# ingredionradar.net
KiCad netlist of a schematic drawn in Altium Designer
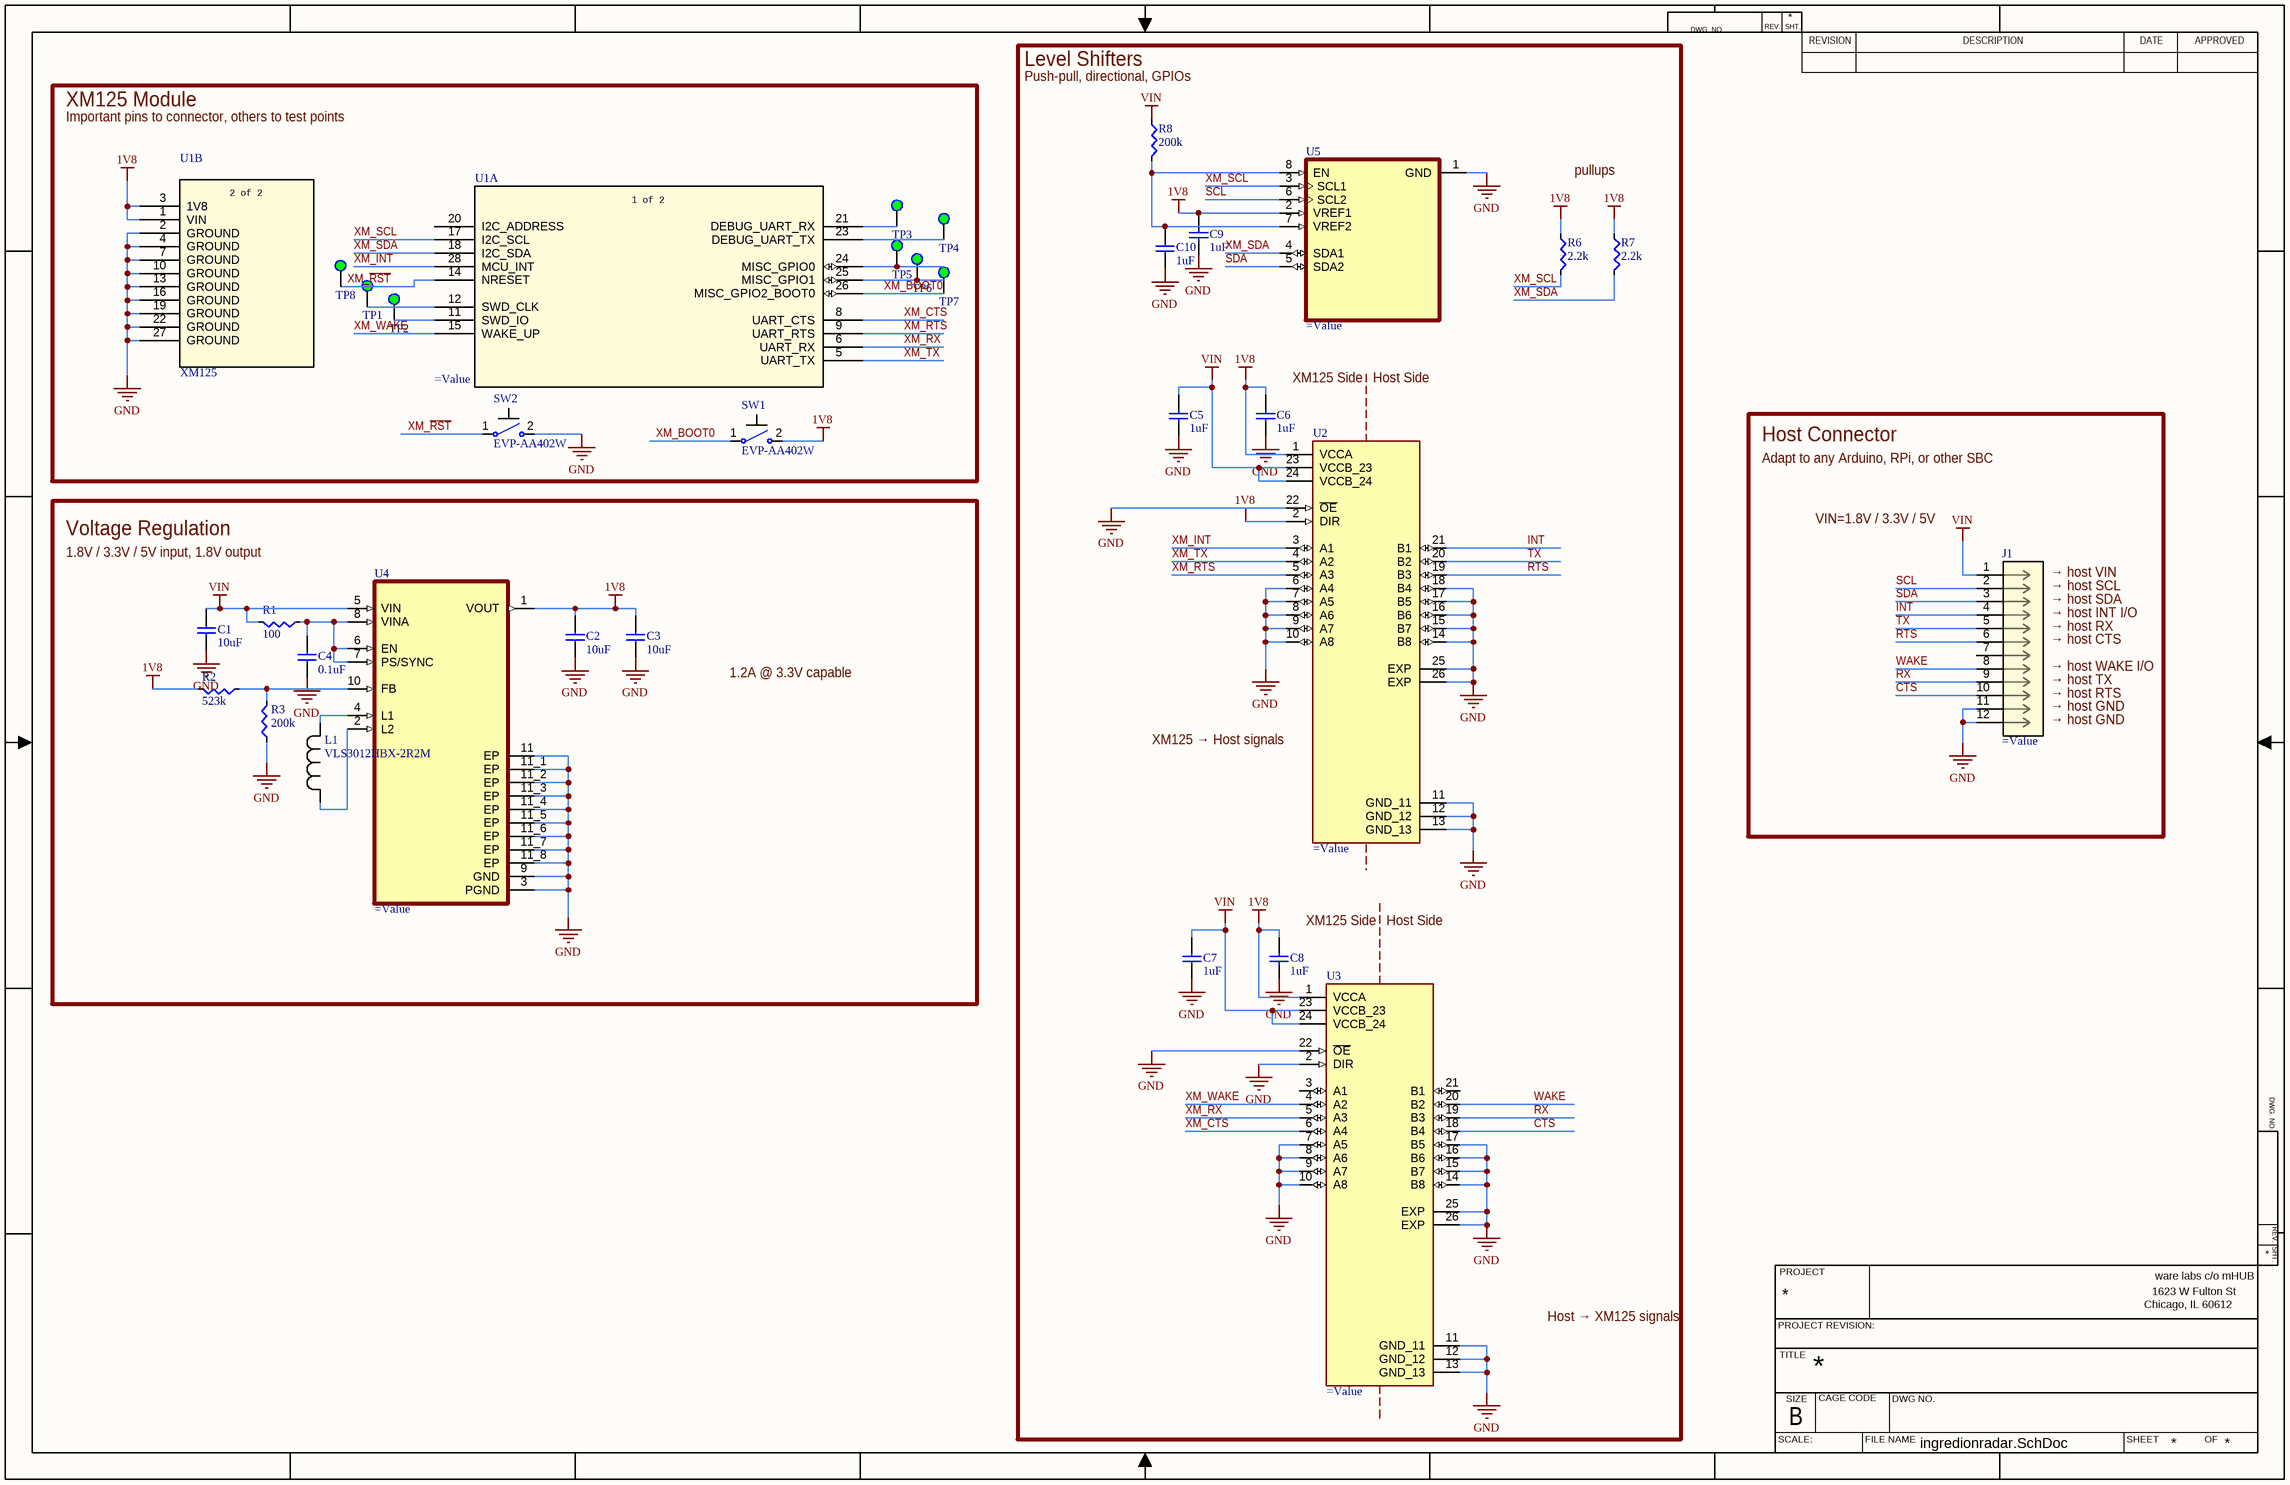
[diagram p0: ingredionradar.SchDoc]

(export (version "E")
  (design (tool "Eeschema 10.0.6"))
  (components
    (comp (ref "C1")
      (value "10uF")
      (footprint "CAP0603")
      (description "Chip Capacitor")
      (fields
        (field (name "MANUFACTURER") "Samsung Electro-Mechanics")
        (field (name "PART NUMBER") "CL10X106MO8NRNC")
      )
      (libsource (lib "ware") (part "CAP"))
    )
    (comp (ref "C2")
      (value "10uF")
      (footprint "CAP0603")
      (description "Chip Capacitor")
      (fields
        (field (name "MANUFACTURER") "Samsung Electro-Mechanics")
        (field (name "PART NUMBER") "CL10X106MO8NRNC")
      )
      (libsource (lib "ware") (part "CAP"))
    )
    (comp (ref "C3")
      (value "10uF")
      (footprint "CAP0603")
      (description "Chip Capacitor")
      (fields
        (field (name "MANUFACTURER") "Samsung Electro-Mechanics")
        (field (name "PART NUMBER") "CL10X106MO8NRNC")
      )
      (libsource (lib "ware") (part "CAP"))
    )
    (comp (ref "C4")
      (value "0.1uF")
      (footprint "CAP0402")
      (description "Chip Capacitor")
      (fields
        (field (name "MANUFACTURER") "Samsung Electro-Mechanics")
        (field (name "PART NUMBER") "CL05B104KP5NNNC")
      )
      (libsource (lib "ware") (part "CAP"))
    )
    (comp (ref "C5")
      (value "1uF")
      (footprint "CAP0402")
      (description "Chip Capacitor")
      (fields
        (field (name "MANUFACTURER") "Samsung Electro-Mechanics")
        (field (name "PART NUMBER") "CL05B105KQ5NQNC")
      )
      (libsource (lib "ware") (part "CAP"))
    )
    (comp (ref "C6")
      (value "1uF")
      (footprint "CAP0402")
      (description "Chip Capacitor")
      (fields
        (field (name "MANUFACTURER") "Samsung Electro-Mechanics")
        (field (name "PART NUMBER") "CL05B105KQ5NQNC")
      )
      (libsource (lib "ware") (part "CAP"))
    )
    (comp (ref "C7")
      (value "1uF")
      (footprint "CAP0402")
      (description "Chip Capacitor")
      (fields
        (field (name "MANUFACTURER") "Samsung Electro-Mechanics")
        (field (name "PART NUMBER") "CL05B105KQ5NQNC")
      )
      (libsource (lib "ware") (part "CAP"))
    )
    (comp (ref "C8")
      (value "1uF")
      (footprint "CAP0402")
      (description "Chip Capacitor")
      (fields
        (field (name "MANUFACTURER") "Samsung Electro-Mechanics")
        (field (name "PART NUMBER") "CL05B105KQ5NQNC")
      )
      (libsource (lib "ware") (part "CAP"))
    )
    (comp (ref "C9")
      (value "1uF")
      (footprint "CAP0402")
      (description "Chip Capacitor")
      (fields
        (field (name "MANUFACTURER") "Samsung Electro-Mechanics")
        (field (name "PART NUMBER") "CL05B105KQ5NQNC")
      )
      (libsource (lib "ware") (part "CAP"))
    )
    (comp (ref "C10")
      (value "1uF")
      (footprint "CAP0402")
      (description "Chip Capacitor")
      (fields
        (field (name "MANUFACTURER") "Samsung Electro-Mechanics")
        (field (name "PART NUMBER") "CL05B105KQ5NQNC")
      )
      (libsource (lib "ware") (part "CAP"))
    )
    (comp (ref "J1")
      (value "~")
      (footprint "CONN_SM12B-SRSS-TBLFSN_JST")
      (description "Description")
      (fields
        (field (name "MANUFACTURER") "JST Sales America Inc.")
        (field (name "PART NUMBER") "SM12B-SRSS-TB")
      )
      (libsource (lib "SM12B-SRSS-TBLFSN") (part "SM12B-SRSS-TBLFSN"))
    )
    (comp (ref "L1")
      (value "VLS3012HBX-2R2M")
      (footprint "IND_VLS3012HBX_TDK")
      (description "Description")
      (fields (field (name "MANUFACTURER") "TDK Corporation"))
      (libsource (lib "VLS3012HBX-2R2M") (part "VLS3012HBX-2R2M"))
    )
    (comp (ref "R1")
      (value "100")
      (footprint "RES0402")
      (description "Chip Resistor")
      (fields
        (field (name "MANUFACTURER") "Samsung Electro-Mechanics")
        (field (name "PART NUMBER") "RCS1005F101CS")
      )
      (libsource (lib "ware") (part "RES"))
    )
    (comp (ref "R2")
      (value "523k")
      (footprint "RES0402")
      (description "Chip Resistor")
      (fields
        (field (name "MANUFACTURER") "Samsung Electro-Mechanics")
        (field (name "PART NUMBER") "RCS1005F5233CS")
      )
      (libsource (lib "ware") (part "RES"))
    )
    (comp (ref "R3")
      (value "200k")
      (footprint "RES0402")
      (description "Chip Resistor")
      (fields
        (field (name "MANUFACTURER") "Samsung Electro-Mechanics")
        (field (name "PART NUMBER") "RCS1005F204CS")
      )
      (libsource (lib "ware") (part "RES"))
    )
    (comp (ref "R6")
      (value "2.2k")
      (footprint "RES0402")
      (description "Chip Resistor")
      (fields
        (field (name "MANUFACTURER") "Samsung Electro-Mechanics")
        (field (name "PART NUMBER") "RC1005F222CS")
      )
      (libsource (lib "ware") (part "RES"))
    )
    (comp (ref "R7")
      (value "2.2k")
      (footprint "RES0402")
      (description "Chip Resistor")
      (fields
        (field (name "MANUFACTURER") "Samsung Electro-Mechanics")
        (field (name "PART NUMBER") "RC1005F222CS")
      )
      (libsource (lib "ware") (part "RES"))
    )
    (comp (ref "R8")
      (value "200k")
      (footprint "RES0402")
      (description "Chip Resistor")
      (fields
        (field (name "MANUFACTURER") "Samsung Electro-Mechanics")
        (field (name "PART NUMBER") "RC1005J204CS")
      )
      (libsource (lib "ware") (part "RES"))
    )
    (comp (ref "SW1")
      (value "EVP-AA402W")
      (footprint "EVPXA")
      (description "SPST, Off-Mom, no ground pin")
      (libsource (lib "ware") (part "SW_TACT"))
    )
    (comp (ref "SW2")
      (value "EVP-AA402W")
      (footprint "EVPXA")
      (description "SPST, Off-Mom, no ground pin")
      (libsource (lib "ware") (part "SW_TACT"))
    )
    (comp (ref "TP1")
      (value "TP_SMT")
      (footprint "TP_SMT_1.5MM")
      (description "Test point")
      (libsource (lib "ware") (part "Test Point"))
    )
    (comp (ref "TP2")
      (value "TP_SMT")
      (footprint "TP_SMT_1.5MM")
      (description "Test point")
      (libsource (lib "ware") (part "Test Point"))
    )
    (comp (ref "TP3")
      (value "TP_SMT")
      (footprint "TP_SMT_1.5MM")
      (description "Test point")
      (libsource (lib "ware") (part "Test Point"))
    )
    (comp (ref "TP4")
      (value "TP_SMT")
      (footprint "TP_SMT_1.5MM")
      (description "Test point")
      (libsource (lib "ware") (part "Test Point"))
    )
    (comp (ref "TP5")
      (value "TP_SMT")
      (footprint "TP_SMT_1.5MM")
      (description "Test point")
      (libsource (lib "ware") (part "Test Point"))
    )
    (comp (ref "TP6")
      (value "TP_SMT")
      (footprint "TP_SMT_1.5MM")
      (description "Test point")
      (libsource (lib "ware") (part "Test Point"))
    )
    (comp (ref "TP7")
      (value "TP_SMT")
      (footprint "TP_SMT_1.5MM")
      (description "Test point")
      (libsource (lib "ware") (part "Test Point"))
    )
    (comp (ref "TP8")
      (value "TP_SMT")
      (footprint "TP_SMT_1.5MM")
      (description "Test point")
      (libsource (lib "ware") (part "Test Point"))
    )
    (comp (ref "U1")
      (value "XM125")
      (footprint "XM125_ACC")
      (description "Description")
      (fields (field (name "MANUFACTURER") "Acconeer AB") (field (name "PART NUMBER") "XM125"))
      (libsource (lib "XM125") (part "XM125"))
    )
    (comp (ref "U2")
      (value "~")
      (footprint "IC_SN74LVC8T245RHLR")
      (fields
        (field (name "MANUFACTURER") "Texas Instruments")
        (field (name "PART NUMBER") "SN74LVC8T245RHLR")
      )
      (libsource (lib "SN74LVC8T245RHLR") (part "SN74LVC8T245RHLR"))
    )
    (comp (ref "U3")
      (value "~")
      (footprint "IC_SN74LVC8T245RHLR")
      (fields
        (field (name "MANUFACTURER") "Texas Instruments")
        (field (name "PART NUMBER") "SN74LVC8T245RHLR")
      )
      (libsource (lib "SN74LVC8T245RHLR") (part "SN74LVC8T245RHLR"))
    )
    (comp (ref "U4")
      (value "~")
      (footprint "CONV_TPS63000DRCR")
      (description "96% Buck-Boost Converter with 1.8A Current Switches in 3x3 QFN 10-VSON -40 to 85")
      (fields (field (name "MANUFACTURER") "Texas Instruments") (field (name "PART NUMBER") "TPS63000DRCR"))
      (libsource (lib "TPS63000DRCR") (part "TPS63000DRCR"))
    )
    (comp (ref "U5")
      (value "~")
      (footprint "SON35P140X100X40-8N")
      (description "2-bit bidirectional 400-kHz I2C/SMBus voltage level translator")
      (fields (field (name "MANUFACTURER") "Texas Instruments") (field (name "PART NUMBER") "PCA9306DQER"))
      (libsource (lib "PCA9306DQER") (part "PCA9306DQER"))
    )
  )
  (nets
    (net (code "1") (name "/CTS") (class "Default")
      (node (ref "J1") (pin "10") (pinfunction "10_10") (pintype "passive"))
      (node (ref "U3") (pin "18") (pinfunction "B4_18") (pintype "bidirectional"))
    )
    (net (code "2") (name "/INT") (class "Default")
      (node (ref "J1") (pin "4") (pinfunction "4_4") (pintype "passive"))
      (node (ref "U2") (pin "21") (pinfunction "B1_21") (pintype "bidirectional"))
    )
    (net (code "3") (name "/RTS") (class "Default")
      (node (ref "J1") (pin "6") (pinfunction "6_6") (pintype "passive"))
      (node (ref "U2") (pin "19") (pinfunction "B3_19") (pintype "bidirectional"))
    )
    (net (code "4") (name "/RX") (class "Default")
      (node (ref "J1") (pin "9") (pinfunction "9_9") (pintype "passive"))
      (node (ref "U3") (pin "19") (pinfunction "B3_19") (pintype "bidirectional"))
    )
    (net (code "5") (name "/SCL") (class "Default")
      (node (ref "J1") (pin "2") (pinfunction "2_2") (pintype "passive"))
      (node (ref "U5") (pin "6") (pinfunction "SCL2_6") (pintype "input"))
    )
    (net (code "6") (name "/SDA") (class "Default")
      (node (ref "J1") (pin "3") (pinfunction "3_3") (pintype "passive"))
      (node (ref "U5") (pin "5") (pinfunction "SDA2_5") (pintype "bidirectional"))
    )
    (net (code "7") (name "/TX") (class "Default")
      (node (ref "J1") (pin "5") (pinfunction "5_5") (pintype "passive"))
      (node (ref "U2") (pin "20") (pinfunction "B2_20") (pintype "bidirectional"))
    )
    (net (code "8") (name "/WAKE") (class "Default")
      (node (ref "J1") (pin "8") (pinfunction "8_8") (pintype "passive"))
      (node (ref "U3") (pin "20") (pinfunction "B2_20") (pintype "bidirectional"))
    )
    (net (code "9") (name "/XM_BOOT0") (class "Default")
      (node (ref "SW1") (pin "1") (pinfunction "1_1") (pintype "passive"))
      (node (ref "TP7") (pin "1") (pinfunction "TP_1") (pintype "passive"))
      (node (ref "U1") (pin "26") (pinfunction "MISC_GPIO2_BOOT0_26") (pintype "bidirectional"))
    )
    (net (code "10") (name "/XM_CTS") (class "Default")
      (node (ref "U1") (pin "8") (pinfunction "UART_CTS_8") (pintype "passive"))
      (node (ref "U3") (pin "6") (pinfunction "A4_6") (pintype "bidirectional"))
    )
    (net (code "11") (name "/XM_INT") (class "Default")
      (node (ref "U1") (pin "28") (pinfunction "MCU_INT_28") (pintype "passive"))
      (node (ref "U2") (pin "3") (pinfunction "A1_3") (pintype "bidirectional"))
    )
    (net (code "12") (name "/XM_RTS") (class "Default")
      (node (ref "U1") (pin "9") (pinfunction "UART_RTS_9") (pintype "passive"))
      (node (ref "U2") (pin "5") (pinfunction "A3_5") (pintype "bidirectional"))
    )
    (net (code "13") (name "/XM_RX") (class "Default")
      (node (ref "U1") (pin "6") (pinfunction "UART_RX_6") (pintype "passive"))
      (node (ref "U3") (pin "5") (pinfunction "A3_5") (pintype "bidirectional"))
    )
    (net (code "14") (name "/XM_SCL") (class "Default")
      (node (ref "R6") (pin "2") (pinfunction "2_2") (pintype "passive"))
      (node (ref "U1") (pin "17") (pinfunction "I2C_SCL_17") (pintype "passive"))
      (node (ref "U5") (pin "3") (pinfunction "SCL1_3") (pintype "input"))
    )
    (net (code "15") (name "/XM_SDA") (class "Default")
      (node (ref "R7") (pin "2") (pinfunction "2_2") (pintype "passive"))
      (node (ref "U1") (pin "18") (pinfunction "I2C_SDA_18") (pintype "passive"))
      (node (ref "U5") (pin "4") (pinfunction "SDA1_4") (pintype "bidirectional"))
    )
    (net (code "16") (name "/XM_TX") (class "Default")
      (node (ref "U1") (pin "5") (pinfunction "UART_TX_5") (pintype "passive"))
      (node (ref "U2") (pin "4") (pinfunction "A2_4") (pintype "bidirectional"))
    )
    (net (code "17") (name "/XM_WAKE") (class "Default")
      (node (ref "U1") (pin "15") (pinfunction "WAKE_UP_15") (pintype "passive"))
      (node (ref "U3") (pin "4") (pinfunction "A2_4") (pintype "bidirectional"))
    )
    (net (code "18") (name "/XM_~{RST}") (class "Default")
      (node (ref "SW2") (pin "1") (pinfunction "1_1") (pintype "passive"))
      (node (ref "TP8") (pin "1") (pinfunction "TP_1") (pintype "passive"))
      (node (ref "U1") (pin "14") (pinfunction "NRESET_14") (pintype "passive"))
    )
    (net (code "19") (name "1V8") (class "Default")
      (node (ref "C2") (pin "2") (pinfunction "2_2") (pintype "passive"))
      (node (ref "C3") (pin "2") (pinfunction "2_2") (pintype "passive"))
      (node (ref "C6") (pin "2") (pinfunction "2_2") (pintype "passive"))
      (node (ref "C8") (pin "2") (pinfunction "2_2") (pintype "passive"))
      (node (ref "C9") (pin "2") (pinfunction "2_2") (pintype "passive"))
      (node (ref "R2") (pin "2") (pinfunction "2_2") (pintype "passive"))
      (node (ref "R6") (pin "1") (pinfunction "1_1") (pintype "passive"))
      (node (ref "R7") (pin "1") (pinfunction "1_1") (pintype "passive"))
      (node (ref "SW1") (pin "2") (pinfunction "2_2") (pintype "passive"))
      (node (ref "U1") (pin "1") (pinfunction "VIN_1") (pintype "power_in"))
      (node (ref "U1") (pin "3") (pinfunction "1V8_3") (pintype "power_in"))
      (node (ref "U2") (pin "1") (pinfunction "VCCA_1") (pintype "power_in"))
      (node (ref "U2") (pin "2") (pinfunction "DIR_2") (pintype "input"))
      (node (ref "U3") (pin "1") (pinfunction "VCCA_1") (pintype "power_in"))
      (node (ref "U4") (pin "1") (pinfunction "VOUT_1") (pintype "output"))
      (node (ref "U5") (pin "2") (pinfunction "VREF1_2") (pintype "input"))
    )
    (net (code "20") (name "GND") (class "Default")
      (node (ref "C1") (pin "1") (pinfunction "1_1") (pintype "passive"))
      (node (ref "C10") (pin "1") (pinfunction "1_1") (pintype "passive"))
      (node (ref "C2") (pin "1") (pinfunction "1_1") (pintype "passive"))
      (node (ref "C3") (pin "1") (pinfunction "1_1") (pintype "passive"))
      (node (ref "C4") (pin "1") (pinfunction "1_1") (pintype "passive"))
      (node (ref "C5") (pin "1") (pinfunction "1_1") (pintype "passive"))
      (node (ref "C6") (pin "1") (pinfunction "1_1") (pintype "passive"))
      (node (ref "C7") (pin "1") (pinfunction "1_1") (pintype "passive"))
      (node (ref "C8") (pin "1") (pinfunction "1_1") (pintype "passive"))
      (node (ref "C9") (pin "1") (pinfunction "1_1") (pintype "passive"))
      (node (ref "J1") (pin "11") (pinfunction "11_11") (pintype "passive"))
      (node (ref "J1") (pin "12") (pinfunction "12_12") (pintype "passive"))
      (node (ref "R3") (pin "1") (pinfunction "1_1") (pintype "passive"))
      (node (ref "SW2") (pin "2") (pinfunction "2_2") (pintype "passive"))
      (node (ref "U1") (pin "10") (pinfunction "GROUND_10") (pintype "power_in"))
      (node (ref "U1") (pin "13") (pinfunction "GROUND_13") (pintype "power_in"))
      (node (ref "U1") (pin "16") (pinfunction "GROUND_16") (pintype "power_in"))
      (node (ref "U1") (pin "19") (pinfunction "GROUND_19") (pintype "power_in"))
      (node (ref "U1") (pin "2") (pinfunction "GROUND_2") (pintype "power_in"))
      (node (ref "U1") (pin "22") (pinfunction "GROUND_22") (pintype "power_in"))
      (node (ref "U1") (pin "27") (pinfunction "GROUND_27") (pintype "power_in"))
      (node (ref "U1") (pin "4") (pinfunction "GROUND_4") (pintype "power_in"))
      (node (ref "U1") (pin "7") (pinfunction "GROUND_7") (pintype "power_in"))
      (node (ref "U2") (pin "10") (pinfunction "A8_10") (pintype "bidirectional"))
      (node (ref "U2") (pin "11") (pinfunction "GND_11_11") (pintype "power_in"))
      (node (ref "U2") (pin "12") (pinfunction "GND_12_12") (pintype "power_in"))
      (node (ref "U2") (pin "13") (pinfunction "GND_13_13") (pintype "power_in"))
      (node (ref "U2") (pin "14") (pinfunction "B8_14") (pintype "bidirectional"))
      (node (ref "U2") (pin "15") (pinfunction "B7_15") (pintype "bidirectional"))
      (node (ref "U2") (pin "16") (pinfunction "B6_16") (pintype "bidirectional"))
      (node (ref "U2") (pin "17") (pinfunction "B5_17") (pintype "bidirectional"))
      (node (ref "U2") (pin "18") (pinfunction "B4_18") (pintype "bidirectional"))
      (node (ref "U2") (pin "22") (pinfunction "~{OE}_22") (pintype "input"))
      (node (ref "U2") (pin "25") (pinfunction "EXP_25") (pintype "passive"))
      (node (ref "U2") (pin "26") (pinfunction "EXP_26") (pintype "passive"))
      (node (ref "U2") (pin "6") (pinfunction "A4_6") (pintype "bidirectional"))
      (node (ref "U2") (pin "7") (pinfunction "A5_7") (pintype "bidirectional"))
      (node (ref "U2") (pin "8") (pinfunction "A6_8") (pintype "bidirectional"))
      (node (ref "U2") (pin "9") (pinfunction "A7_9") (pintype "bidirectional"))
      (node (ref "U3") (pin "10") (pinfunction "A8_10") (pintype "bidirectional"))
      (node (ref "U3") (pin "11") (pinfunction "GND_11_11") (pintype "power_in"))
      (node (ref "U3") (pin "12") (pinfunction "GND_12_12") (pintype "power_in"))
      (node (ref "U3") (pin "13") (pinfunction "GND_13_13") (pintype "power_in"))
      (node (ref "U3") (pin "14") (pinfunction "B8_14") (pintype "bidirectional"))
      (node (ref "U3") (pin "15") (pinfunction "B7_15") (pintype "bidirectional"))
      (node (ref "U3") (pin "16") (pinfunction "B6_16") (pintype "bidirectional"))
      (node (ref "U3") (pin "17") (pinfunction "B5_17") (pintype "bidirectional"))
      (node (ref "U3") (pin "2") (pinfunction "DIR_2") (pintype "input"))
      (node (ref "U3") (pin "22") (pinfunction "~{OE}_22") (pintype "input"))
      (node (ref "U3") (pin "25") (pinfunction "EXP_25") (pintype "passive"))
      (node (ref "U3") (pin "26") (pinfunction "EXP_26") (pintype "passive"))
      (node (ref "U3") (pin "7") (pinfunction "A5_7") (pintype "bidirectional"))
      (node (ref "U3") (pin "8") (pinfunction "A6_8") (pintype "bidirectional"))
      (node (ref "U3") (pin "9") (pinfunction "A7_9") (pintype "bidirectional"))
      (node (ref "U4") (pin "11") (pinfunction "EP_11") (pintype "power_in"))
      (node (ref "U4") (pin "11_1") (pinfunction "EP_11_1") (pintype "power_in"))
      (node (ref "U4") (pin "11_2") (pinfunction "EP_11_2") (pintype "power_in"))
      (node (ref "U4") (pin "11_3") (pinfunction "EP_11_3") (pintype "power_in"))
      (node (ref "U4") (pin "11_4") (pinfunction "EP_11_4") (pintype "power_in"))
      (node (ref "U4") (pin "11_5") (pinfunction "EP_11_5") (pintype "power_in"))
      (node (ref "U4") (pin "11_6") (pinfunction "EP_11_6") (pintype "power_in"))
      (node (ref "U4") (pin "11_7") (pinfunction "EP_11_7") (pintype "power_in"))
      (node (ref "U4") (pin "11_8") (pinfunction "EP_11_8") (pintype "power_in"))
      (node (ref "U4") (pin "3") (pinfunction "PGND_3") (pintype "power_in"))
      (node (ref "U4") (pin "9") (pinfunction "GND_9") (pintype "power_in"))
      (node (ref "U5") (pin "1") (pinfunction "GND_1") (pintype "power_in"))
    )
    (net (code "21") (name "Net-(TP1-TP)") (class "Default")
      (node (ref "TP1") (pin "1") (pinfunction "TP_1") (pintype "passive"))
      (node (ref "U1") (pin "12") (pinfunction "SWD_CLK_12") (pintype "passive"))
    )
    (net (code "22") (name "Net-(TP2-TP)") (class "Default")
      (node (ref "TP2") (pin "1") (pinfunction "TP_1") (pintype "passive"))
      (node (ref "U1") (pin "11") (pinfunction "SWD_IO_11") (pintype "passive"))
    )
    (net (code "23") (name "Net-(TP3-TP)") (class "Default")
      (node (ref "TP3") (pin "1") (pinfunction "TP_1") (pintype "passive"))
      (node (ref "U1") (pin "21") (pinfunction "DEBUG_UART_RX_21") (pintype "passive"))
    )
    (net (code "24") (name "Net-(TP4-TP)") (class "Default")
      (node (ref "TP4") (pin "1") (pinfunction "TP_1") (pintype "passive"))
      (node (ref "U1") (pin "23") (pinfunction "DEBUG_UART_TX_23") (pintype "passive"))
    )
    (net (code "25") (name "Net-(TP5-TP)") (class "Default")
      (node (ref "TP5") (pin "1") (pinfunction "TP_1") (pintype "passive"))
      (node (ref "U1") (pin "24") (pinfunction "MISC_GPIO0_24") (pintype "bidirectional"))
    )
    (net (code "26") (name "Net-(TP6-TP)") (class "Default")
      (node (ref "TP6") (pin "1") (pinfunction "TP_1") (pintype "passive"))
      (node (ref "U1") (pin "25") (pinfunction "MISC_GPIO1_25") (pintype "bidirectional"))
    )
    (net (code "27") (name "Net-(U4-EN)") (class "Default")
      (node (ref "C4") (pin "2") (pinfunction "2_2") (pintype "passive"))
      (node (ref "R1") (pin "1") (pinfunction "1_1") (pintype "passive"))
      (node (ref "U4") (pin "6") (pinfunction "EN_6") (pintype "input"))
      (node (ref "U4") (pin "7") (pinfunction "PS/SYNC_7") (pintype "input"))
      (node (ref "U4") (pin "8") (pinfunction "VINA_8") (pintype "input"))
    )
    (net (code "28") (name "Net-(U4-FB)") (class "Default")
      (node (ref "R2") (pin "1") (pinfunction "1_1") (pintype "passive"))
      (node (ref "R3") (pin "2") (pinfunction "2_2") (pintype "passive"))
      (node (ref "U4") (pin "10") (pinfunction "FB_10") (pintype "input"))
    )
    (net (code "29") (name "Net-(U4-L1)") (class "Default")
      (node (ref "L1") (pin "1") (pinfunction "1_1") (pintype "passive"))
      (node (ref "U4") (pin "4") (pinfunction "L1_4") (pintype "input"))
    )
    (net (code "30") (name "Net-(U4-L2)") (class "Default")
      (node (ref "L1") (pin "2") (pinfunction "2_2") (pintype "passive"))
      (node (ref "U4") (pin "2") (pinfunction "L2_2") (pintype "input"))
    )
    (net (code "31") (name "Net-(U5-EN)") (class "Default")
      (node (ref "C10") (pin "2") (pinfunction "2_2") (pintype "passive"))
      (node (ref "R8") (pin "2") (pinfunction "2_2") (pintype "passive"))
      (node (ref "U5") (pin "7") (pinfunction "VREF2_7") (pintype "input"))
      (node (ref "U5") (pin "8") (pinfunction "EN_8") (pintype "input"))
    )
    (net (code "32") (name "VIN") (class "Default")
      (node (ref "C1") (pin "2") (pinfunction "2_2") (pintype "passive"))
      (node (ref "C5") (pin "2") (pinfunction "2_2") (pintype "passive"))
      (node (ref "C7") (pin "2") (pinfunction "2_2") (pintype "passive"))
      (node (ref "J1") (pin "1") (pinfunction "1_1") (pintype "passive"))
      (node (ref "R1") (pin "2") (pinfunction "2_2") (pintype "passive"))
      (node (ref "R8") (pin "1") (pinfunction "1_1") (pintype "passive"))
      (node (ref "U2") (pin "23") (pinfunction "VCCB_23_23") (pintype "power_in"))
      (node (ref "U2") (pin "24") (pinfunction "VCCB_24_24") (pintype "power_in"))
      (node (ref "U3") (pin "23") (pinfunction "VCCB_23_23") (pintype "power_in"))
      (node (ref "U3") (pin "24") (pinfunction "VCCB_24_24") (pintype "power_in"))
      (node (ref "U4") (pin "5") (pinfunction "VIN_5") (pintype "input"))
    )
    (net (code "33") (name "unconnected-(J1-Pad7)") (class "Default")
      (node (ref "J1") (pin "7") (pinfunction "7_7") (pintype "passive"))
    )
    (net (code "34") (name "unconnected-(U1A-I2C_ADDRESS-Pad20)") (class "Default")
      (node (ref "U1") (pin "20") (pinfunction "I2C_ADDRESS_20") (pintype "passive"))
    )
    (net (code "35") (name "unconnected-(U3-A1-Pad3)") (class "Default")
      (node (ref "U3") (pin "3") (pinfunction "A1_3") (pintype "bidirectional"))
    )
    (net (code "36") (name "unconnected-(U3-B1-Pad21)") (class "Default")
      (node (ref "U3") (pin "21") (pinfunction "B1_21") (pintype "bidirectional"))
    )
  )
)
